# fire_filter.net
KiCad netlist of a schematic drawn in Altium Designer
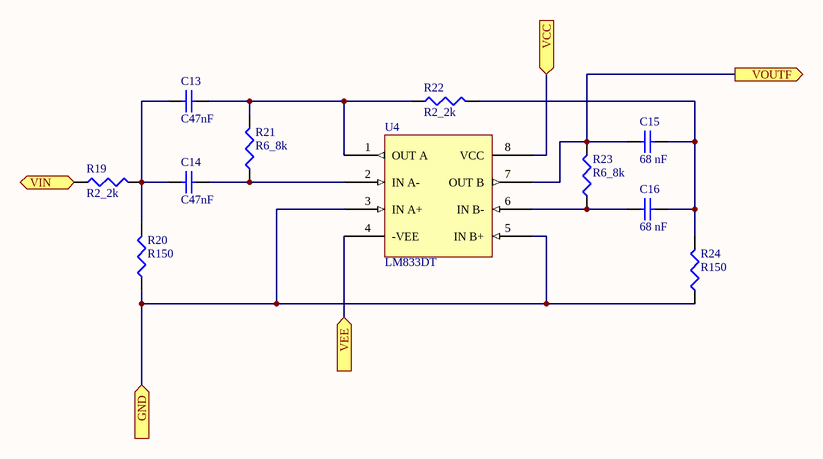
[diagram p0: fire_filter.SchDoc]

(export (version "E")
  (design (tool "Eeschema 10.0.6"))
  (components
    (comp (ref "C13")
      (value "C47nF")
      (footprint "C0603")
      (description "47 nF Surface Mount Capacitor")
      (fields
        (field (name "MANUFACTURER") "Murata Electronics North America")
        (field (name "MANUFACTURER PART NUMBER") "GRM188R71C473KA01D")
      )
      (libsource (lib "Capstone Libraries") (part "C47nF"))
    )
    (comp (ref "C14")
      (value "C47nF")
      (footprint "C0603")
      (description "47 nF Surface Mount Capacitor")
      (fields
        (field (name "MANUFACTURER") "Murata Electronics North America")
        (field (name "MANUFACTURER PART NUMBER") "GRM188R71C473KA01D")
      )
      (libsource (lib "Capstone Libraries") (part "C47nF"))
    )
    (comp (ref "C15")
      (value "68 nF")
      (footprint "C0603")
      (description "68 nF Surface Mount Capacitor")
      (fields
        (field (name "MANUFACTURER") "Murata Electronics North America")
        (field (name "MANUFACTURER PART NUMBER") "GRM188R71E683KA01D")
      )
      (libsource (lib "Capstone Libraries") (part "C68nF"))
    )
    (comp (ref "C16")
      (value "68 nF")
      (footprint "C0603")
      (description "68 nF Surface Mount Capacitor")
      (fields
        (field (name "MANUFACTURER") "Murata Electronics North America")
        (field (name "MANUFACTURER PART NUMBER") "GRM188R71E683KA01D")
      )
      (libsource (lib "Capstone Libraries") (part "C68nF"))
    )
    (comp (ref "R19")
      (value "R2_2k")
      (footprint "R0603")
      (description "2.2k Ohms Surface Mount Resistor")
      (fields
        (field (name "MANUFACTURER") "Yageo")
        (field (name "MANUFACTURER PART NUMBER") "RC0603FR-072K2L")
      )
      (libsource (lib "Capstone Libraries") (part "R2_2k"))
    )
    (comp (ref "R20")
      (value "R150")
      (footprint "R0603")
      (description "150 Ohms Surface Mount Resistor")
      (fields
        (field (name "MANUFACTURER") "Yageo")
        (field (name "MANUFACTURER PART NUMBER") "RC0603FR-07150RL")
      )
      (libsource (lib "Capstone Libraries") (part "R150"))
    )
    (comp (ref "R21")
      (value "R6_8k")
      (footprint "R0603")
      (description "6.8k Ohms Surface Mount Resistor")
      (fields
        (field (name "MANUFACTURER") "Panasonic Electronic Components")
        (field (name "MANUFACTURER PART NUMBER") "ERJ-3EKF6801V")
      )
      (libsource (lib "Capstone Libraries") (part "R6_8k"))
    )
    (comp (ref "R22")
      (value "R2_2k")
      (footprint "R0603")
      (description "2.2k Ohms Surface Mount Resistor")
      (fields
        (field (name "MANUFACTURER") "Yageo")
        (field (name "MANUFACTURER PART NUMBER") "RC0603FR-072K2L")
      )
      (libsource (lib "Capstone Libraries") (part "R2_2k"))
    )
    (comp (ref "R23")
      (value "R6_8k")
      (footprint "R0603")
      (description "6.8k Ohms Surface Mount Resistor")
      (fields
        (field (name "MANUFACTURER") "Panasonic Electronic Components")
        (field (name "MANUFACTURER PART NUMBER") "ERJ-3EKF6801V")
      )
      (libsource (lib "Capstone Libraries") (part "R6_8k"))
    )
    (comp (ref "R24")
      (value "R150")
      (footprint "R0603")
      (description "150 Ohms Surface Mount Resistor")
      (fields
        (field (name "MANUFACTURER") "Yageo")
        (field (name "MANUFACTURER PART NUMBER") "RC0603FR-07150RL")
      )
      (libsource (lib "Capstone Libraries") (part "R150"))
    )
    (comp (ref "U4")
      (value "LM833DT")
      (footprint "soic8")
      (description "IC Dual Audio Amplifier")
      (fields (field (name "MANUFACTURER") "STMicroelectronics"))
      (libsource (lib "Capstone Libraries") (part "LM833DT"))
    )
  )
  (nets
    (net (code "1") (name "/GND") (class "Default")
      (node (ref "R20") (pin "1") (pinfunction "1_1") (pintype "passive"))
      (node (ref "R24") (pin "1") (pinfunction "1_1") (pintype "passive"))
      (node (ref "U4") (pin "3") (pinfunction "IN_A+_3") (pintype "input"))
      (node (ref "U4") (pin "5") (pinfunction "IN_B+_5") (pintype "input"))
    )
    (net (code "2") (name "/VCC") (class "Default")
      (node (ref "U4") (pin "8") (pinfunction "VCC_8") (pintype "passive"))
    )
    (net (code "3") (name "/VEE") (class "Default")
      (node (ref "U4") (pin "4") (pinfunction "-VEE_4") (pintype "passive"))
    )
    (net (code "4") (name "/VIN") (class "Default")
      (node (ref "R19") (pin "1") (pinfunction "1_1") (pintype "passive"))
    )
    (net (code "5") (name "/VOUTF") (class "Default")
      (node (ref "C15") (pin "1") (pinfunction "1_1") (pintype "passive"))
      (node (ref "R23") (pin "2") (pinfunction "2_2") (pintype "passive"))
      (node (ref "U4") (pin "7") (pinfunction "OUT_B_7") (pintype "output"))
    )
    (net (code "6") (name "Net-(C13-Pad1)") (class "Default")
      (node (ref "C13") (pin "1") (pinfunction "1_1") (pintype "passive"))
      (node (ref "C14") (pin "1") (pinfunction "1_1") (pintype "passive"))
      (node (ref "R19") (pin "2") (pinfunction "2_2") (pintype "passive"))
      (node (ref "R20") (pin "2") (pinfunction "2_2") (pintype "passive"))
    )
    (net (code "7") (name "Net-(C15-Pad2)") (class "Default")
      (node (ref "C15") (pin "2") (pinfunction "2_2") (pintype "passive"))
      (node (ref "C16") (pin "2") (pinfunction "2_2") (pintype "passive"))
      (node (ref "R22") (pin "2") (pinfunction "2_2") (pintype "passive"))
      (node (ref "R24") (pin "2") (pinfunction "2_2") (pintype "passive"))
    )
    (net (code "8") (name "Net-(U4-IN_A-)") (class "Default")
      (node (ref "C14") (pin "2") (pinfunction "2_2") (pintype "passive"))
      (node (ref "R21") (pin "1") (pinfunction "1_1") (pintype "passive"))
      (node (ref "U4") (pin "2") (pinfunction "IN_A-_2") (pintype "input"))
    )
    (net (code "9") (name "Net-(U4-IN_B-)") (class "Default")
      (node (ref "C16") (pin "1") (pinfunction "1_1") (pintype "passive"))
      (node (ref "R23") (pin "1") (pinfunction "1_1") (pintype "passive"))
      (node (ref "U4") (pin "6") (pinfunction "IN_B-_6") (pintype "input"))
    )
    (net (code "10") (name "Net-(U4-OUT_A)") (class "Default")
      (node (ref "C13") (pin "2") (pinfunction "2_2") (pintype "passive"))
      (node (ref "R21") (pin "2") (pinfunction "2_2") (pintype "passive"))
      (node (ref "R22") (pin "1") (pinfunction "1_1") (pintype "passive"))
      (node (ref "U4") (pin "1") (pinfunction "OUT_A_1") (pintype "output"))
    )
  )
)
